# perfusion_esquematico.net
KiCad netlist of a schematic drawn in EAGLE
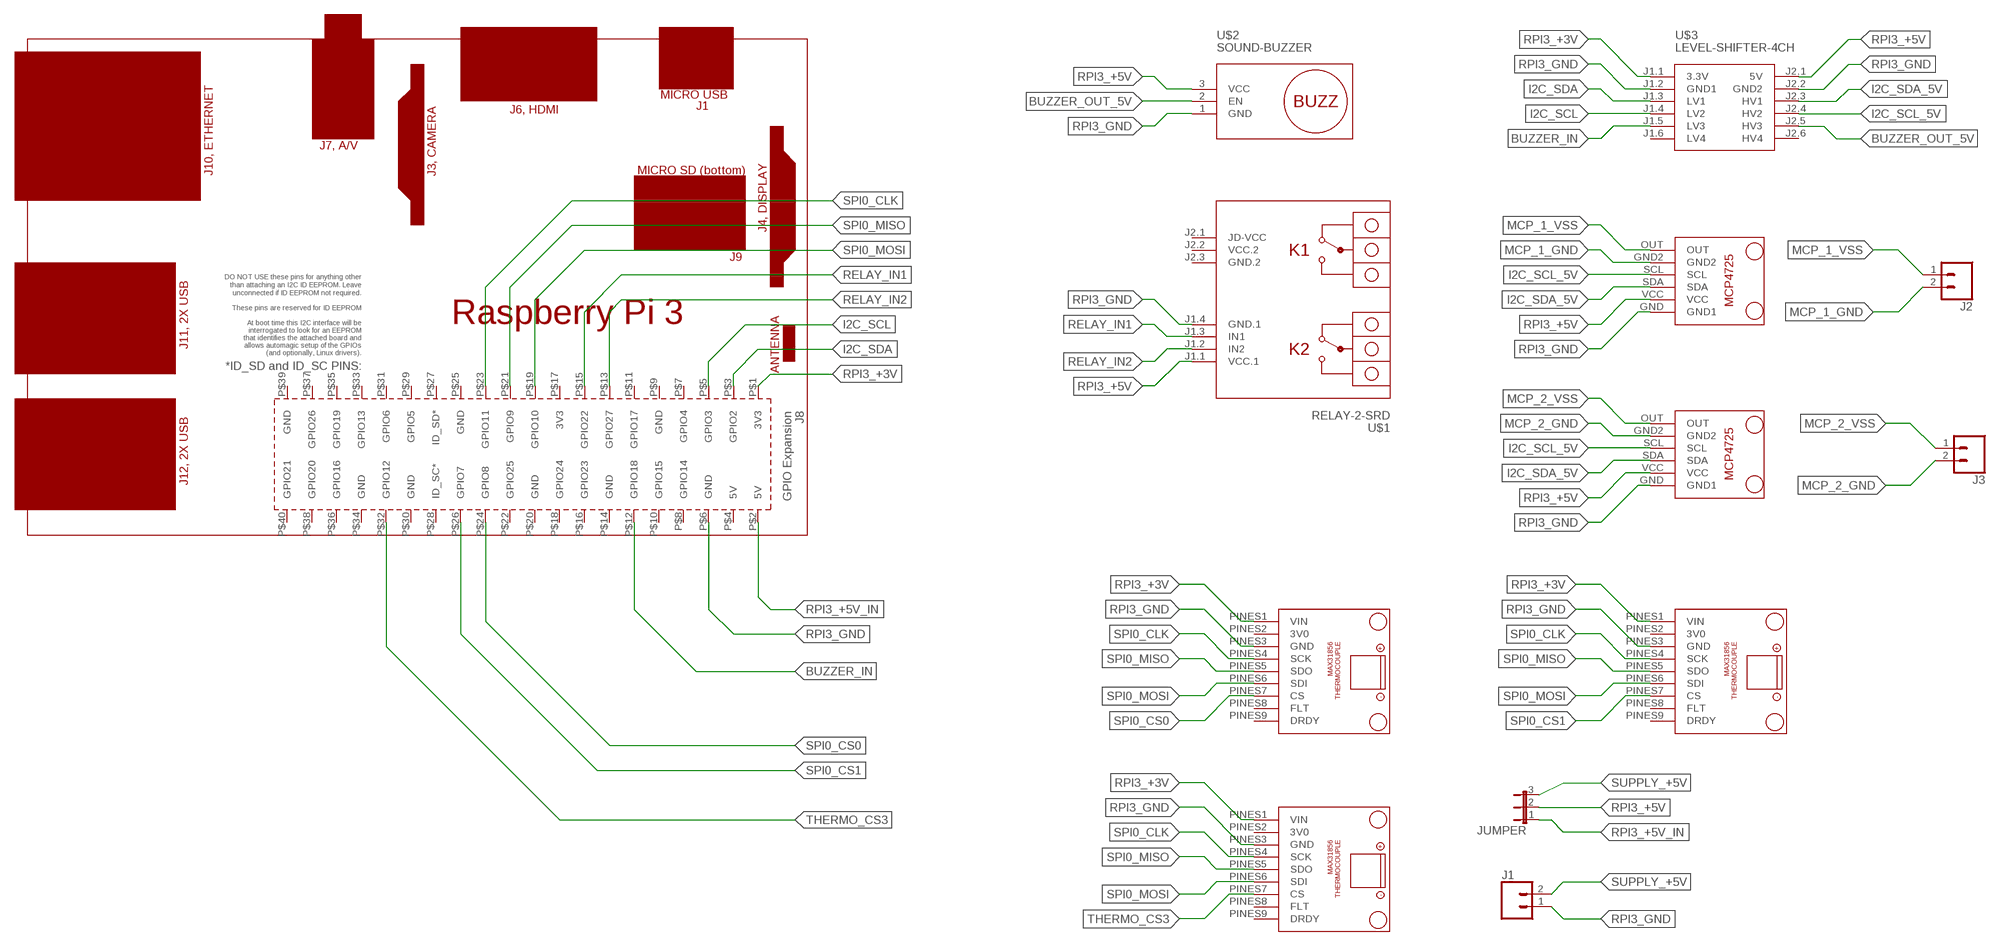
[diagram p0: schematic, sheet 1]

(export (version "E")
  (design (tool "Eeschema 10.0.6"))
  (components
    (comp (ref "J1")
      (value "CONN_023.5MM_LOCK")
      (footprint "eagle-import:SCREWTERMINAL-3.5MM-2_LOCK")
      (libsource (lib "eagle-import") (part "CONN_023.5MM_LOCK"))
    )
    (comp (ref "J2")
      (value "CONN_023.5MM_LOCK")
      (footprint "eagle-import:SCREWTERMINAL-3.5MM-2_LOCK")
      (libsource (lib "eagle-import") (part "CONN_023.5MM_LOCK"))
    )
    (comp (ref "J3")
      (value "CONN_023.5MM_LOCK")
      (footprint "eagle-import:SCREWTERMINAL-3.5MM-2_LOCK")
      (libsource (lib "eagle-import") (part "CONN_023.5MM_LOCK"))
    )
    (comp (ref "JUMPER")
      (value "JP2E")
      (footprint "eagle-import:JP2")
      (libsource (lib "eagle-import") (part "JP2E"))
    )
    (comp (ref "PCB1")
      (value "RPI3")
      (footprint "eagle-import:RPI3")
      (libsource (lib "eagle-import") (part "RPI3"))
    )
    (comp (ref "U$1")
      (value "RELAY-2-SRD")
      (footprint "eagle-import:RELAY-2-SRD")
      (libsource (lib "eagle-import") (part "RELAY-2-SRD"))
    )
    (comp (ref "U$2")
      (value "SOUND-BUZZER")
      (footprint "eagle-import:SOUND-BUZZER")
      (libsource (lib "eagle-import") (part "SOUND-BUZZER"))
    )
    (comp (ref "U$3")
      (value "LEVEL-SHIFTER-4CH")
      (footprint "eagle-import:LEVEL-SHIFTER-4CH")
      (libsource (lib "eagle-import") (part "LEVEL-SHIFTER-4CH"))
    )
    (comp (ref "U$4")
      (value "MAX31856")
      (footprint "eagle-import:MAX31856")
      (libsource (lib "eagle-import") (part "MAX31856"))
    )
    (comp (ref "U$5")
      (value "MAX31856")
      (footprint "eagle-import:MAX31856")
      (libsource (lib "eagle-import") (part "MAX31856"))
    )
    (comp (ref "U$6")
      (value "MAX31856")
      (footprint "eagle-import:MAX31856")
      (libsource (lib "eagle-import") (part "MAX31856"))
    )
    (comp (ref "U$7")
      (value "LIB1MCP4725_ABF")
      (footprint "eagle-import:LIB1")
      (libsource (lib "eagle-import") (part "LIB1MCP4725_ABF"))
    )
    (comp (ref "U$8")
      (value "LIB1MCP4725_ABF")
      (footprint "eagle-import:LIB1")
      (libsource (lib "eagle-import") (part "LIB1MCP4725_ABF"))
    )
  )
  (nets
    (net (code "1") (name "/GND.2") (class "Default")
      (node (ref "U$1") (pin "J2.3") (pinfunction "GND.2_J2.3") (pintype "power_in"))
    )
    (net (code "2") (name "/VCC.2") (class "Default")
      (node (ref "U$1") (pin "J2.2") (pinfunction "VCC.2_J2.2") (pintype "power_in"))
    )
    (net (code "3") (name "BUZZER_IN") (class "Default")
      (node (ref "PCB1") (pin "P$12") (pinfunction "GPIO18_P$12") (pintype "bidirectional"))
      (node (ref "U$3") (pin "J1.5") (pinfunction "LV3_J1.5") (pintype "bidirectional"))
    )
    (net (code "4") (name "BUZZER_OUT_5V") (class "Default")
      (node (ref "U$2") (pin "2") (pinfunction "EN_2") (pintype "input"))
      (node (ref "U$3") (pin "J2.5") (pinfunction "HV3_J2.5") (pintype "bidirectional"))
    )
    (net (code "5") (name "I2C_SCL") (class "Default")
      (node (ref "PCB1") (pin "P$5") (pinfunction "GPIO3_P$5") (pintype "bidirectional"))
      (node (ref "U$3") (pin "J1.4") (pinfunction "LV2_J1.4") (pintype "bidirectional"))
    )
    (net (code "6") (name "I2C_SCL_5V") (class "Default")
      (node (ref "U$3") (pin "J2.4") (pinfunction "HV2_J2.4") (pintype "bidirectional"))
      (node (ref "U$7") (pin "SCL") (pinfunction "SCL_SCL") (pintype "bidirectional"))
      (node (ref "U$8") (pin "SCL") (pinfunction "SCL_SCL") (pintype "bidirectional"))
    )
    (net (code "7") (name "I2C_SDA") (class "Default")
      (node (ref "PCB1") (pin "P$3") (pinfunction "GPIO2_P$3") (pintype "bidirectional"))
      (node (ref "U$3") (pin "J1.3") (pinfunction "LV1_J1.3") (pintype "bidirectional"))
    )
    (net (code "8") (name "I2C_SDA_5V") (class "Default")
      (node (ref "U$3") (pin "J2.3") (pinfunction "HV1_J2.3") (pintype "bidirectional"))
      (node (ref "U$7") (pin "SDA") (pinfunction "SDA_SDA") (pintype "bidirectional"))
      (node (ref "U$8") (pin "SDA") (pinfunction "SDA_SDA") (pintype "bidirectional"))
    )
    (net (code "9") (name "MCP_1_GND") (class "Default")
      (node (ref "J2") (pin "2") (pinfunction "2_2") (pintype "passive"))
      (node (ref "U$8") (pin "GND2") (pinfunction "GND2_GND2") (pintype "bidirectional"))
    )
    (net (code "10") (name "MCP_1_VSS") (class "Default")
      (node (ref "J2") (pin "1") (pinfunction "1_1") (pintype "passive"))
      (node (ref "U$8") (pin "OUT") (pinfunction "OUT_OUT") (pintype "bidirectional"))
    )
    (net (code "11") (name "MCP_2_GND") (class "Default")
      (node (ref "J3") (pin "2") (pinfunction "2_2") (pintype "passive"))
      (node (ref "U$7") (pin "GND2") (pinfunction "GND2_GND2") (pintype "bidirectional"))
    )
    (net (code "12") (name "MCP_2_VSS") (class "Default")
      (node (ref "J3") (pin "1") (pinfunction "1_1") (pintype "passive"))
      (node (ref "U$7") (pin "OUT") (pinfunction "OUT_OUT") (pintype "bidirectional"))
    )
    (net (code "13") (name "RELAY_IN1") (class "Default")
      (node (ref "PCB1") (pin "P$15") (pinfunction "GPIO22_P$15") (pintype "bidirectional"))
      (node (ref "U$1") (pin "J1.3") (pinfunction "IN1_J1.3") (pintype "bidirectional"))
    )
    (net (code "14") (name "RELAY_IN2") (class "Default")
      (node (ref "PCB1") (pin "P$13") (pinfunction "GPIO27_P$13") (pintype "bidirectional"))
      (node (ref "U$1") (pin "J1.2") (pinfunction "IN2_J1.2") (pintype "bidirectional"))
    )
    (net (code "15") (name "RPI3_+3V") (class "Default")
      (node (ref "PCB1") (pin "P$1") (pinfunction "3V3_P$1") (pintype "bidirectional"))
      (node (ref "U$3") (pin "J1.1") (pinfunction "3.3V_J1.1") (pintype "power_in"))
      (node (ref "U$4") (pin "PINES1") (pinfunction "VIN_PINES1") (pintype "bidirectional"))
      (node (ref "U$5") (pin "PINES1") (pinfunction "VIN_PINES1") (pintype "bidirectional"))
      (node (ref "U$6") (pin "PINES1") (pinfunction "VIN_PINES1") (pintype "bidirectional"))
    )
    (net (code "16") (name "RPI3_+5V") (class "Default")
      (node (ref "JUMPER") (pin "2") (pinfunction "2_2") (pintype "passive"))
      (node (ref "U$1") (pin "J1.1") (pinfunction "VCC.1_J1.1") (pintype "power_in"))
      (node (ref "U$2") (pin "3") (pinfunction "VCC_3") (pintype "power_in"))
      (node (ref "U$3") (pin "J2.1") (pinfunction "5V_J2.1") (pintype "power_in"))
      (node (ref "U$7") (pin "VCC") (pinfunction "VCC_VCC") (pintype "bidirectional"))
      (node (ref "U$8") (pin "VCC") (pinfunction "VCC_VCC") (pintype "bidirectional"))
    )
    (net (code "17") (name "RPI3_+5V_IN") (class "Default")
      (node (ref "JUMPER") (pin "1") (pinfunction "1_1") (pintype "passive"))
      (node (ref "PCB1") (pin "P$2") (pinfunction "5V_P$2") (pintype "bidirectional"))
    )
    (net (code "18") (name "RPI3_GND") (class "Default")
      (node (ref "J1") (pin "1") (pinfunction "1_1") (pintype "passive"))
      (node (ref "PCB1") (pin "P$6") (pinfunction "GND_P$6") (pintype "bidirectional"))
      (node (ref "U$1") (pin "J1.4") (pinfunction "GND.1_J1.4") (pintype "power_in"))
      (node (ref "U$2") (pin "1") (pinfunction "GND_1") (pintype "power_in"))
      (node (ref "U$3") (pin "J1.2") (pinfunction "GND1_J1.2") (pintype "power_in"))
      (node (ref "U$3") (pin "J2.2") (pinfunction "GND2_J2.2") (pintype "power_in"))
      (node (ref "U$4") (pin "PINES3") (pinfunction "GND_PINES3") (pintype "bidirectional"))
      (node (ref "U$5") (pin "PINES3") (pinfunction "GND_PINES3") (pintype "bidirectional"))
      (node (ref "U$6") (pin "PINES3") (pinfunction "GND_PINES3") (pintype "bidirectional"))
      (node (ref "U$7") (pin "GND") (pinfunction "GND1_GND") (pintype "bidirectional"))
      (node (ref "U$8") (pin "GND") (pinfunction "GND1_GND") (pintype "bidirectional"))
    )
    (net (code "19") (name "SPI0_CLK") (class "Default")
      (node (ref "PCB1") (pin "P$23") (pinfunction "GPIO11_P$23") (pintype "bidirectional"))
      (node (ref "U$4") (pin "PINES4") (pinfunction "SCK_PINES4") (pintype "bidirectional"))
      (node (ref "U$5") (pin "PINES4") (pinfunction "SCK_PINES4") (pintype "bidirectional"))
      (node (ref "U$6") (pin "PINES4") (pinfunction "SCK_PINES4") (pintype "bidirectional"))
    )
    (net (code "20") (name "SPI0_CS0") (class "Default")
      (node (ref "PCB1") (pin "P$24") (pinfunction "GPIO8_P$24") (pintype "bidirectional"))
      (node (ref "U$4") (pin "PINES7") (pinfunction "CS_PINES7") (pintype "bidirectional"))
    )
    (net (code "21") (name "SPI0_CS1") (class "Default")
      (node (ref "PCB1") (pin "P$26") (pinfunction "GPIO7_P$26") (pintype "bidirectional"))
      (node (ref "U$5") (pin "PINES7") (pinfunction "CS_PINES7") (pintype "bidirectional"))
    )
    (net (code "22") (name "SPI0_MISO") (class "Default")
      (node (ref "PCB1") (pin "P$21") (pinfunction "GPIO9_P$21") (pintype "bidirectional"))
      (node (ref "U$4") (pin "PINES5") (pinfunction "SDO_PINES5") (pintype "bidirectional"))
      (node (ref "U$5") (pin "PINES5") (pinfunction "SDO_PINES5") (pintype "bidirectional"))
      (node (ref "U$6") (pin "PINES5") (pinfunction "SDO_PINES5") (pintype "bidirectional"))
    )
    (net (code "23") (name "SPI0_MOSI") (class "Default")
      (node (ref "PCB1") (pin "P$19") (pinfunction "GPIO10_P$19") (pintype "bidirectional"))
      (node (ref "U$4") (pin "PINES6") (pinfunction "SDI_PINES6") (pintype "bidirectional"))
      (node (ref "U$5") (pin "PINES6") (pinfunction "SDI_PINES6") (pintype "bidirectional"))
      (node (ref "U$6") (pin "PINES6") (pinfunction "SDI_PINES6") (pintype "bidirectional"))
    )
    (net (code "24") (name "SUPPLY_+5V") (class "Default")
      (node (ref "J1") (pin "2") (pinfunction "2_2") (pintype "passive"))
      (node (ref "JUMPER") (pin "3") (pinfunction "3_3") (pintype "passive"))
    )
    (net (code "25") (name "THERMO_CS3") (class "Default")
      (node (ref "PCB1") (pin "P$32") (pinfunction "GPIO12_P$32") (pintype "bidirectional"))
      (node (ref "U$6") (pin "PINES7") (pinfunction "CS_PINES7") (pintype "bidirectional"))
    )
    (net (code "26") (name "unconnected-(PCB1-3V3-PadP$17)") (class "Default")
      (node (ref "PCB1") (pin "P$17") (pinfunction "3V3_P$17") (pintype "bidirectional"))
    )
    (net (code "27") (name "unconnected-(PCB1-5V-PadP$4)") (class "Default")
      (node (ref "PCB1") (pin "P$4") (pinfunction "5V_P$4") (pintype "bidirectional"))
    )
    (net (code "28") (name "unconnected-(PCB1-GND-PadP$9)") (class "Default")
      (node (ref "PCB1") (pin "P$9") (pinfunction "GND_P$9") (pintype "bidirectional"))
    )
    (net (code "29") (name "unconnected-(PCB1-GND-PadP$14)") (class "Default")
      (node (ref "PCB1") (pin "P$14") (pinfunction "GND_P$14") (pintype "bidirectional"))
    )
    (net (code "30") (name "unconnected-(PCB1-GND-PadP$20)") (class "Default")
      (node (ref "PCB1") (pin "P$20") (pinfunction "GND_P$20") (pintype "bidirectional"))
    )
    (net (code "31") (name "unconnected-(PCB1-GND-PadP$25)") (class "Default")
      (node (ref "PCB1") (pin "P$25") (pinfunction "GND_P$25") (pintype "bidirectional"))
    )
    (net (code "32") (name "unconnected-(PCB1-GND-PadP$30)") (class "Default")
      (node (ref "PCB1") (pin "P$30") (pinfunction "GND_P$30") (pintype "bidirectional"))
    )
    (net (code "33") (name "unconnected-(PCB1-GND-PadP$34)") (class "Default")
      (node (ref "PCB1") (pin "P$34") (pinfunction "GND_P$34") (pintype "bidirectional"))
    )
    (net (code "34") (name "unconnected-(PCB1-GND-PadP$39)") (class "Default")
      (node (ref "PCB1") (pin "P$39") (pinfunction "GND_P$39") (pintype "bidirectional"))
    )
    (net (code "35") (name "unconnected-(PCB1-GPIO4-PadP$7)") (class "Default")
      (node (ref "PCB1") (pin "P$7") (pinfunction "GPIO4_P$7") (pintype "bidirectional"))
    )
    (net (code "36") (name "unconnected-(PCB1-GPIO5-PadP$29)") (class "Default")
      (node (ref "PCB1") (pin "P$29") (pinfunction "GPIO5_P$29") (pintype "bidirectional"))
    )
    (net (code "37") (name "unconnected-(PCB1-GPIO6-PadP$31)") (class "Default")
      (node (ref "PCB1") (pin "P$31") (pinfunction "GPIO6_P$31") (pintype "bidirectional"))
    )
    (net (code "38") (name "unconnected-(PCB1-GPIO13-PadP$33)") (class "Default")
      (node (ref "PCB1") (pin "P$33") (pinfunction "GPIO13_P$33") (pintype "bidirectional"))
    )
    (net (code "39") (name "unconnected-(PCB1-GPIO14-PadP$8)") (class "Default")
      (node (ref "PCB1") (pin "P$8") (pinfunction "GPIO14_P$8") (pintype "bidirectional"))
    )
    (net (code "40") (name "unconnected-(PCB1-GPIO15-PadP$10)") (class "Default")
      (node (ref "PCB1") (pin "P$10") (pinfunction "GPIO15_P$10") (pintype "bidirectional"))
    )
    (net (code "41") (name "unconnected-(PCB1-GPIO16-PadP$36)") (class "Default")
      (node (ref "PCB1") (pin "P$36") (pinfunction "GPIO16_P$36") (pintype "bidirectional"))
    )
    (net (code "42") (name "unconnected-(PCB1-GPIO17-PadP$11)") (class "Default")
      (node (ref "PCB1") (pin "P$11") (pinfunction "GPIO17_P$11") (pintype "bidirectional"))
    )
    (net (code "43") (name "unconnected-(PCB1-GPIO19-PadP$35)") (class "Default")
      (node (ref "PCB1") (pin "P$35") (pinfunction "GPIO19_P$35") (pintype "bidirectional"))
    )
    (net (code "44") (name "unconnected-(PCB1-GPIO20-PadP$38)") (class "Default")
      (node (ref "PCB1") (pin "P$38") (pinfunction "GPIO20_P$38") (pintype "bidirectional"))
    )
    (net (code "45") (name "unconnected-(PCB1-GPIO21-PadP$40)") (class "Default")
      (node (ref "PCB1") (pin "P$40") (pinfunction "GPIO21_P$40") (pintype "bidirectional"))
    )
    (net (code "46") (name "unconnected-(PCB1-GPIO23-PadP$16)") (class "Default")
      (node (ref "PCB1") (pin "P$16") (pinfunction "GPIO23_P$16") (pintype "bidirectional"))
    )
    (net (code "47") (name "unconnected-(PCB1-GPIO24-PadP$18)") (class "Default")
      (node (ref "PCB1") (pin "P$18") (pinfunction "GPIO24_P$18") (pintype "bidirectional"))
    )
    (net (code "48") (name "unconnected-(PCB1-GPIO25-PadP$22)") (class "Default")
      (node (ref "PCB1") (pin "P$22") (pinfunction "GPIO25_P$22") (pintype "bidirectional"))
    )
    (net (code "49") (name "unconnected-(PCB1-GPIO26-PadP$37)") (class "Default")
      (node (ref "PCB1") (pin "P$37") (pinfunction "GPIO26_P$37") (pintype "bidirectional"))
    )
    (net (code "50") (name "unconnected-(PCB1-ID_SC*-PadP$28)") (class "Default")
      (node (ref "PCB1") (pin "P$28") (pinfunction "ID_SC*_P$28") (pintype "bidirectional"))
    )
    (net (code "51") (name "unconnected-(PCB1-ID_SD*-PadP$27)") (class "Default")
      (node (ref "PCB1") (pin "P$27") (pinfunction "ID_SD*_P$27") (pintype "bidirectional"))
    )
    (net (code "52") (name "unconnected-(U$1-JD-VCC-PadJ2.1)") (class "Default")
      (node (ref "U$1") (pin "J2.1") (pinfunction "JD-VCC_J2.1") (pintype "bidirectional"))
    )
    (net (code "53") (name "unconnected-(U$3-HV4-PadJ2.6)") (class "Default")
      (node (ref "U$3") (pin "J2.6") (pinfunction "HV4_J2.6") (pintype "bidirectional"))
    )
    (net (code "54") (name "unconnected-(U$3-LV4-PadJ1.6)") (class "Default")
      (node (ref "U$3") (pin "J1.6") (pinfunction "LV4_J1.6") (pintype "bidirectional"))
    )
    (net (code "55") (name "unconnected-(U$4-3V0-PadPINES2)") (class "Default")
      (node (ref "U$4") (pin "PINES2") (pinfunction "3V0_PINES2") (pintype "bidirectional"))
    )
    (net (code "56") (name "unconnected-(U$4-DRDY-PadPINES9)") (class "Default")
      (node (ref "U$4") (pin "PINES9") (pinfunction "DRDY_PINES9") (pintype "bidirectional"))
    )
    (net (code "57") (name "unconnected-(U$4-FLT-PadPINES8)") (class "Default")
      (node (ref "U$4") (pin "PINES8") (pinfunction "FLT_PINES8") (pintype "bidirectional"))
    )
    (net (code "58") (name "unconnected-(U$5-3V0-PadPINES2)") (class "Default")
      (node (ref "U$5") (pin "PINES2") (pinfunction "3V0_PINES2") (pintype "bidirectional"))
    )
    (net (code "59") (name "unconnected-(U$5-DRDY-PadPINES9)") (class "Default")
      (node (ref "U$5") (pin "PINES9") (pinfunction "DRDY_PINES9") (pintype "bidirectional"))
    )
    (net (code "60") (name "unconnected-(U$5-FLT-PadPINES8)") (class "Default")
      (node (ref "U$5") (pin "PINES8") (pinfunction "FLT_PINES8") (pintype "bidirectional"))
    )
    (net (code "61") (name "unconnected-(U$6-3V0-PadPINES2)") (class "Default")
      (node (ref "U$6") (pin "PINES2") (pinfunction "3V0_PINES2") (pintype "bidirectional"))
    )
    (net (code "62") (name "unconnected-(U$6-DRDY-PadPINES9)") (class "Default")
      (node (ref "U$6") (pin "PINES9") (pinfunction "DRDY_PINES9") (pintype "bidirectional"))
    )
    (net (code "63") (name "unconnected-(U$6-FLT-PadPINES8)") (class "Default")
      (node (ref "U$6") (pin "PINES8") (pinfunction "FLT_PINES8") (pintype "bidirectional"))
    )
  )
)
